# communication.net
KiCad netlist of a schematic drawn in EAGLE
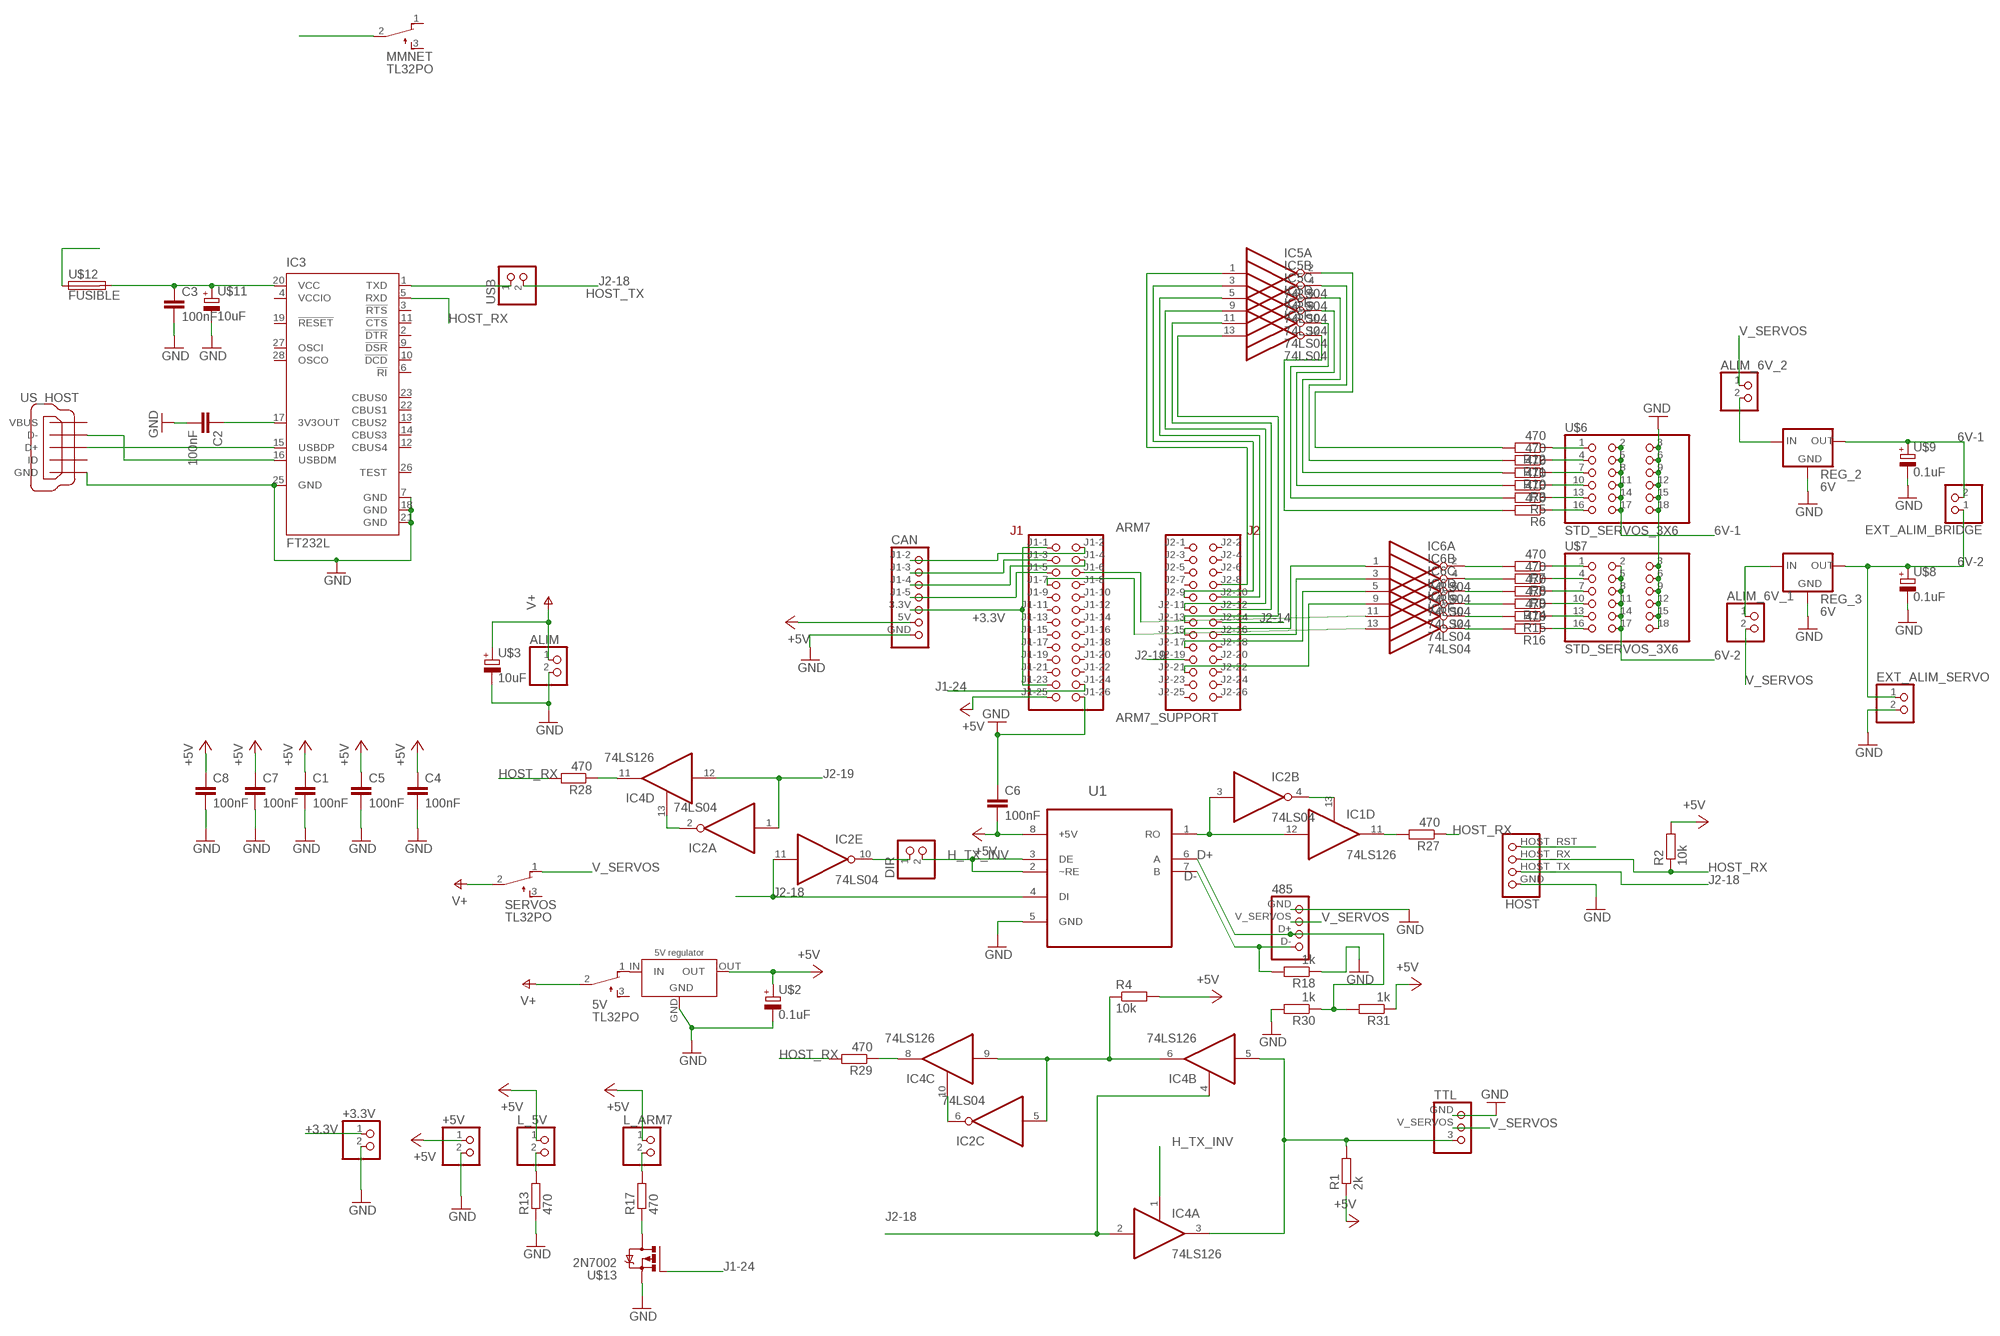
[diagram p0: schematic, sheet 1]

(export (version "E")
  (design (tool "Eeschema 10.0.6"))
  (components
    (comp (ref "+3.3V")
      (value "CONNEC_1X02")
      (footprint "eagle-import:CONNEC_1X02")
      (libsource (lib "eagle-import") (part "CONNEC_1X02"))
    )
    (comp (ref "+5V")
      (value "CONNEC_1X02")
      (footprint "eagle-import:CONNEC_1X02")
      (libsource (lib "eagle-import") (part "CONNEC_1X02"))
    )
    (comp (ref "5V")
      (value "TL32PO")
      (footprint "eagle-import:TL3XPO")
      (libsource (lib "eagle-import") (part "TL32PO"))
    )
    (comp (ref "485")
      (value "CONNECTEUR_485")
      (footprint "eagle-import:CONNECTEUR_485")
      (libsource (lib "eagle-import") (part "CONNECTEUR_485"))
    )
    (comp (ref "ALIM")
      (value "CONNEC_1X02CONNEC_1X02_LARGE")
      (footprint "eagle-import:CONNEC_ALIM")
      (libsource (lib "eagle-import") (part "CONNEC_1X02CONNEC_1X02_LARGE"))
    )
    (comp (ref "ALIM_6V_1")
      (value "CONNEC_1X02")
      (footprint "eagle-import:CONNEC_1X02")
      (libsource (lib "eagle-import") (part "CONNEC_1X02"))
    )
    (comp (ref "ALIM_6V_2")
      (value "CONNEC_1X02")
      (footprint "eagle-import:CONNEC_1X02")
      (libsource (lib "eagle-import") (part "CONNEC_1X02"))
    )
    (comp (ref "ARM7")
      (value "ARM7_SUPPORT")
      (footprint "eagle-import:ARM7_SUPPORT")
      (libsource (lib "eagle-import") (part "ARM7_SUPPORT"))
    )
    (comp (ref "C1")
      (value "100nF")
      (footprint "eagle-import:R0805")
      (libsource (lib "eagle-import") (part "C_EU_0805"))
    )
    (comp (ref "C2")
      (value "100nF")
      (footprint "eagle-import:R0805")
      (libsource (lib "eagle-import") (part "C_EU_0805"))
    )
    (comp (ref "C3")
      (value "100nF")
      (footprint "eagle-import:R0805")
      (libsource (lib "eagle-import") (part "C_EU_0805"))
    )
    (comp (ref "C4")
      (value "100nF")
      (footprint "eagle-import:R0805")
      (libsource (lib "eagle-import") (part "C_EU_0805"))
    )
    (comp (ref "C5")
      (value "100nF")
      (footprint "eagle-import:R0805")
      (libsource (lib "eagle-import") (part "C_EU_0805"))
    )
    (comp (ref "C6")
      (value "100nF")
      (footprint "eagle-import:R0805")
      (libsource (lib "eagle-import") (part "C_EU_0805"))
    )
    (comp (ref "C7")
      (value "100nF")
      (footprint "eagle-import:R0805")
      (libsource (lib "eagle-import") (part "C_EU_0805"))
    )
    (comp (ref "C8")
      (value "100nF")
      (footprint "eagle-import:R0805")
      (libsource (lib "eagle-import") (part "C_EU_0805"))
    )
    (comp (ref "CAN")
      (value "CONNECTEUR_CAN")
      (footprint "eagle-import:CONNECTEUR_CAN")
      (libsource (lib "eagle-import") (part "CONNECTEUR_CAN"))
    )
    (comp (ref "DIR")
      (value "CONNEC_1X02")
      (footprint "eagle-import:CONNEC_1X02")
      (libsource (lib "eagle-import") (part "CONNEC_1X02"))
    )
    (comp (ref "EXT_ALIM_BRIDGE")
      (value "CONNEC_1X02")
      (footprint "eagle-import:CONNEC_1X02")
      (libsource (lib "eagle-import") (part "CONNEC_1X02"))
    )
    (comp (ref "EXT_ALIM_SERVO")
      (value "CONNEC_1X02CONNEC_1X02_LARGE")
      (footprint "eagle-import:CONNEC_ALIM")
      (libsource (lib "eagle-import") (part "CONNEC_1X02CONNEC_1X02_LARGE"))
    )
    (comp (ref "HOST")
      (value "CONNECTOR_HOST")
      (footprint "eagle-import:CONNECTOR_HOST")
      (libsource (lib "eagle-import") (part "CONNECTOR_HOST"))
    )
    (comp (ref "IC1")
      (value "74LS126")
      (footprint "eagle-import:SO14")
      (libsource (lib "eagle-import") (part "74126DLS"))
    )
    (comp (ref "IC2")
      (value "74LS04")
      (footprint "eagle-import:SO14")
      (libsource (lib "eagle-import") (part "7404DLS"))
    )
    (comp (ref "IC3")
      (value "FT232L")
      (footprint "eagle-import:SSOP28")
      (fields (field (name "MPN") "FT232RL"))
      (libsource (lib "eagle-import") (part "FT232L"))
    )
    (comp (ref "IC4")
      (value "74LS126")
      (footprint "eagle-import:SO14")
      (libsource (lib "eagle-import") (part "74126DLS"))
    )
    (comp (ref "IC5")
      (value "74LS04")
      (footprint "eagle-import:SO14")
      (libsource (lib "eagle-import") (part "7404DLS"))
    )
    (comp (ref "IC6")
      (value "74LS04")
      (footprint "eagle-import:SO14")
      (libsource (lib "eagle-import") (part "7404DLS"))
    )
    (comp (ref "L_5V")
      (value "CONNEC_1X02")
      (footprint "eagle-import:CONNEC_1X02")
      (libsource (lib "eagle-import") (part "CONNEC_1X02"))
    )
    (comp (ref "L_ARM7")
      (value "CONNEC_1X02")
      (footprint "eagle-import:CONNEC_1X02")
      (libsource (lib "eagle-import") (part "CONNEC_1X02"))
    )
    (comp (ref "MMNET")
      (value "TL32PO")
      (footprint "eagle-import:TL3XPO")
      (libsource (lib "eagle-import") (part "TL32PO"))
    )
    (comp (ref "R1")
      (value "2k")
      (footprint "eagle-import:R0805@1")
      (libsource (lib "eagle-import") (part "R-EU_R0805"))
    )
    (comp (ref "R2")
      (value "10k")
      (footprint "eagle-import:R0805@1")
      (libsource (lib "eagle-import") (part "R-EU_R0805"))
    )
    (comp (ref "R3")
      (value "470")
      (footprint "eagle-import:R0805@1")
      (libsource (lib "eagle-import") (part "R-EU_R0805"))
    )
    (comp (ref "R4")
      (value "10k")
      (footprint "eagle-import:R0805@1")
      (libsource (lib "eagle-import") (part "R-EU_R0805"))
    )
    (comp (ref "R5")
      (value "470")
      (footprint "eagle-import:R0805@1")
      (libsource (lib "eagle-import") (part "R-EU_R0805"))
    )
    (comp (ref "R6")
      (value "470")
      (footprint "eagle-import:R0805@1")
      (libsource (lib "eagle-import") (part "R-EU_R0805"))
    )
    (comp (ref "R7")
      (value "470")
      (footprint "eagle-import:R0805@1")
      (libsource (lib "eagle-import") (part "R-EU_R0805"))
    )
    (comp (ref "R8")
      (value "470")
      (footprint "eagle-import:R0805@1")
      (libsource (lib "eagle-import") (part "R-EU_R0805"))
    )
    (comp (ref "R9")
      (value "470")
      (footprint "eagle-import:R0805@1")
      (libsource (lib "eagle-import") (part "R-EU_R0805"))
    )
    (comp (ref "R10")
      (value "470")
      (footprint "eagle-import:R0805@1")
      (libsource (lib "eagle-import") (part "R-EU_R0805"))
    )
    (comp (ref "R11")
      (value "470")
      (footprint "eagle-import:R0805@1")
      (libsource (lib "eagle-import") (part "R-EU_R0805"))
    )
    (comp (ref "R12")
      (value "470")
      (footprint "eagle-import:R0805@1")
      (libsource (lib "eagle-import") (part "R-EU_R0805"))
    )
    (comp (ref "R13")
      (value "470")
      (footprint "eagle-import:R0805@1")
      (libsource (lib "eagle-import") (part "R-EU_R0805"))
    )
    (comp (ref "R14")
      (value "470")
      (footprint "eagle-import:R0805@1")
      (libsource (lib "eagle-import") (part "R-EU_R0805"))
    )
    (comp (ref "R15")
      (value "470")
      (footprint "eagle-import:R0805@1")
      (libsource (lib "eagle-import") (part "R-EU_R0805"))
    )
    (comp (ref "R16")
      (value "470")
      (footprint "eagle-import:R0805@1")
      (libsource (lib "eagle-import") (part "R-EU_R0805"))
    )
    (comp (ref "R17")
      (value "470")
      (footprint "eagle-import:R0805@1")
      (libsource (lib "eagle-import") (part "R-EU_R0805"))
    )
    (comp (ref "R18")
      (value "1k")
      (footprint "eagle-import:R0805@1")
      (libsource (lib "eagle-import") (part "R-EU_R0805"))
    )
    (comp (ref "R27")
      (value "470")
      (footprint "eagle-import:R0805@1")
      (libsource (lib "eagle-import") (part "R-EU_R0805"))
    )
    (comp (ref "R28")
      (value "470")
      (footprint "eagle-import:R0805@1")
      (libsource (lib "eagle-import") (part "R-EU_R0805"))
    )
    (comp (ref "R29")
      (value "470")
      (footprint "eagle-import:R0805@1")
      (libsource (lib "eagle-import") (part "R-EU_R0805"))
    )
    (comp (ref "R30")
      (value "1k")
      (footprint "eagle-import:R0805@1")
      (libsource (lib "eagle-import") (part "R-EU_R0805"))
    )
    (comp (ref "R31")
      (value "1k")
      (footprint "eagle-import:R0805@1")
      (libsource (lib "eagle-import") (part "R-EU_R0805"))
    )
    (comp (ref "REG_2")
      (value "6V")
      (footprint "eagle-import:78XXL")
      (libsource (lib "eagle-import") (part "78XXL"))
    )
    (comp (ref "REG_3")
      (value "6V")
      (footprint "eagle-import:78XXL")
      (libsource (lib "eagle-import") (part "78XXL"))
    )
    (comp (ref "SERVOS")
      (value "TL32PO")
      (footprint "eagle-import:TL3XPO")
      (libsource (lib "eagle-import") (part "TL32PO"))
    )
    (comp (ref "TTL")
      (value "CONNECTEUR_TTL")
      (footprint "eagle-import:CONNECTEUR_TTL")
      (libsource (lib "eagle-import") (part "CONNECTEUR_TTL"))
    )
    (comp (ref "U$2")
      (value "0.1uF")
      (footprint "eagle-import:E2,5-6")
      (libsource (lib "eagle-import") (part "CPOL_EUCPOL_EU_2.54-6"))
    )
    (comp (ref "U$3")
      (value "10uF")
      (footprint "eagle-import:E5-10,5")
      (libsource (lib "eagle-import") (part "CPOL_EUCPOL_EU_5-10,5"))
    )
    (comp (ref "U$6")
      (value "STD_SERVOS_3X6")
      (footprint "eagle-import:STD_SERVOS_3X6")
      (libsource (lib "eagle-import") (part "STD_SERVOS_3X6"))
    )
    (comp (ref "U$7")
      (value "STD_SERVOS_3X6")
      (footprint "eagle-import:STD_SERVOS_3X6")
      (libsource (lib "eagle-import") (part "STD_SERVOS_3X6"))
    )
    (comp (ref "U$8")
      (value "0.1uF")
      (footprint "eagle-import:E2,5-6")
      (libsource (lib "eagle-import") (part "CPOL_EUCPOL_EU_2.54-6"))
    )
    (comp (ref "U$9")
      (value "0.1uF")
      (footprint "eagle-import:E2,5-6")
      (libsource (lib "eagle-import") (part "CPOL_EUCPOL_EU_2.54-6"))
    )
    (comp (ref "U$11")
      (value "10uF")
      (footprint "eagle-import:E5-10,5")
      (libsource (lib "eagle-import") (part "CPOL_EUCPOL_EU_5-10,5"))
    )
    (comp (ref "U$12")
      (value "FUSIBLE")
      (footprint "eagle-import:FUSIBLE")
      (libsource (lib "eagle-import") (part "FUSIBLE"))
    )
    (comp (ref "U$13")
      (value "2N7002")
      (footprint "eagle-import:SOT-23")
      (libsource (lib "eagle-import") (part "2N7002"))
    )
    (comp (ref "U$14")
      (value "5V regulator")
      (footprint "eagle-import:REGULATEUR_CMS")
      (libsource (lib "eagle-import") (part "REGULATEUR_CMS"))
    )
    (comp (ref "U1")
      (value "MAX485EESA+")
      (footprint "eagle-import:SOIC127P600X175-8N")
      (libsource (lib "eagle-import") (part "MAX485EESA+"))
    )
    (comp (ref "USB")
      (value "CONNEC_1X02")
      (footprint "eagle-import:CONNEC_1X02")
      (libsource (lib "eagle-import") (part "CONNEC_1X02"))
    )
    (comp (ref "US_HOST")
      (value "MINIUSB")
      (footprint "eagle-import:MINI_USB")
      (libsource (lib "eagle-import") (part "MINIUSB"))
    )
  )
  (nets
    (net (code "1") (name "+5V") (class "Default")
      (node (ref "+5V") (pin "1") (pinfunction "1_1") (pintype "passive"))
      (node (ref "ARM7") (pin "J1-25") (pinfunction "25_J1-25") (pintype "passive"))
      (node (ref "C1") (pin "1") (pinfunction "1_1") (pintype "passive"))
      (node (ref "C3") (pin "1") (pinfunction "1_1") (pintype "passive"))
      (node (ref "C4") (pin "1") (pinfunction "1_1") (pintype "passive"))
      (node (ref "C5") (pin "1") (pinfunction "1_1") (pintype "passive"))
      (node (ref "C6") (pin "2") (pinfunction "2_2") (pintype "passive"))
      (node (ref "C7") (pin "1") (pinfunction "1_1") (pintype "passive"))
      (node (ref "C8") (pin "1") (pinfunction "1_1") (pintype "passive"))
      (node (ref "CAN") (pin "5V") (pinfunction "5V_5V") (pintype "passive"))
      (node (ref "IC3") (pin "20") (pinfunction "VCC_20") (pintype "power_in"))
      (node (ref "L_5V") (pin "1") (pinfunction "1_1") (pintype "passive"))
      (node (ref "L_ARM7") (pin "1") (pinfunction "1_1") (pintype "passive"))
      (node (ref "R1") (pin "1") (pinfunction "1_1") (pintype "passive"))
      (node (ref "R2") (pin "2") (pinfunction "2_2") (pintype "passive"))
      (node (ref "R31") (pin "1") (pinfunction "1_1") (pintype "passive"))
      (node (ref "R4") (pin "2") (pinfunction "2_2") (pintype "passive"))
      (node (ref "U$11") (pin "+") (pinfunction "+_+") (pintype "passive"))
      (node (ref "U$12") (pin "P$1") (pinfunction "1_P$1") (pintype "passive"))
      (node (ref "U$12") (pin "P$2") (pinfunction "2_P$2") (pintype "passive"))
      (node (ref "U$14") (pin "OUT") (pinfunction "OUT_OUT") (pintype "output"))
      (node (ref "U$2") (pin "+") (pinfunction "+_+") (pintype "passive"))
      (node (ref "U1") (pin "8") (pinfunction "+5V_8") (pintype "power_in"))
    )
    (net (code "2") (name "/+3.3V") (class "Default")
      (node (ref "+3.3V") (pin "1") (pinfunction "1_1") (pintype "passive"))
      (node (ref "ARM7") (pin "J1-1") (pinfunction "1_J1-1") (pintype "passive"))
      (node (ref "ARM7") (pin "J1-23") (pinfunction "23_J1-23") (pintype "passive"))
      (node (ref "CAN") (pin "3.3V") (pinfunction "3.3V_3.3V") (pintype "passive"))
    )
    (net (code "3") (name "/6V-1") (class "Default")
      (node (ref "EXT_ALIM_BRIDGE") (pin "2") (pinfunction "2_2") (pintype "passive"))
      (node (ref "REG_2") (pin "OUT") (pinfunction "OUT_OUT") (pintype "passive"))
      (node (ref "U$6") (pin "11") (pinfunction "11_11") (pintype "passive"))
      (node (ref "U$6") (pin "14") (pinfunction "14_14") (pintype "passive"))
      (node (ref "U$6") (pin "17") (pinfunction "17_17") (pintype "passive"))
      (node (ref "U$6") (pin "2") (pinfunction "2_2") (pintype "passive"))
      (node (ref "U$6") (pin "5") (pinfunction "5_5") (pintype "passive"))
      (node (ref "U$6") (pin "8") (pinfunction "8_8") (pintype "passive"))
      (node (ref "U$9") (pin "+") (pinfunction "+_+") (pintype "passive"))
    )
    (net (code "4") (name "/6V-2") (class "Default")
      (node (ref "EXT_ALIM_BRIDGE") (pin "1") (pinfunction "1_1") (pintype "passive"))
      (node (ref "EXT_ALIM_SERVO") (pin "1") (pinfunction "1_1") (pintype "passive"))
      (node (ref "REG_3") (pin "OUT") (pinfunction "OUT_OUT") (pintype "passive"))
      (node (ref "U$7") (pin "11") (pinfunction "11_11") (pintype "passive"))
      (node (ref "U$7") (pin "14") (pinfunction "14_14") (pintype "passive"))
      (node (ref "U$7") (pin "17") (pinfunction "17_17") (pintype "passive"))
      (node (ref "U$7") (pin "2") (pinfunction "2_2") (pintype "passive"))
      (node (ref "U$7") (pin "5") (pinfunction "5_5") (pintype "passive"))
      (node (ref "U$7") (pin "8") (pinfunction "8_8") (pintype "passive"))
      (node (ref "U$8") (pin "+") (pinfunction "+_+") (pintype "passive"))
    )
    (net (code "5") (name "/D+") (class "Default")
      (node (ref "485") (pin "D+") (pinfunction "D+_D+") (pintype "passive"))
      (node (ref "R30") (pin "1") (pinfunction "1_1") (pintype "passive"))
      (node (ref "R31") (pin "2") (pinfunction "2_2") (pintype "passive"))
      (node (ref "U1") (pin "6") (pinfunction "A_6") (pintype "bidirectional"))
    )
    (net (code "6") (name "/D-") (class "Default")
      (node (ref "485") (pin "D-") (pinfunction "D-_D-") (pintype "passive"))
      (node (ref "R18") (pin "2") (pinfunction "2_2") (pintype "passive"))
      (node (ref "U1") (pin "7") (pinfunction "B_7") (pintype "bidirectional"))
    )
    (net (code "7") (name "/HOST_RX") (class "Default")
      (node (ref "HOST") (pin "HOST_RX") (pinfunction "HOST_RX_HOST_RX") (pintype "passive"))
      (node (ref "IC3") (pin "5") (pinfunction "RXD_5") (pintype "input"))
      (node (ref "R2") (pin "1") (pinfunction "1_1") (pintype "passive"))
      (node (ref "R27") (pin "1") (pinfunction "1_1") (pintype "passive"))
      (node (ref "R28") (pin "2") (pinfunction "2_2") (pintype "passive"))
      (node (ref "R29") (pin "2") (pinfunction "2_2") (pintype "passive"))
    )
    (net (code "8") (name "/H_TX_INV") (class "Default")
      (node (ref "DIR") (pin "2") (pinfunction "2_2") (pintype "passive"))
      (node (ref "HOST") (pin "HOST_RST") (pinfunction "HOST_RST_HOST_RST") (pintype "passive"))
      (node (ref "IC4") (pin "1") (pinfunction "OE_1") (pintype "input"))
      (node (ref "U1") (pin "2") (pinfunction "~{RE}_2") (pintype "input"))
      (node (ref "U1") (pin "3") (pinfunction "DE_3") (pintype "input"))
    )
    (net (code "9") (name "/J1-24") (class "Default")
      (node (ref "ARM7") (pin "J1-24") (pinfunction "24_J1-24") (pintype "passive"))
      (node (ref "U$13") (pin "1") (pinfunction "G_1") (pintype "passive"))
    )
    (net (code "10") (name "/J2-14") (class "Default")
      (node (ref "ARM7") (pin "J2-14") (pinfunction "40_J2-14") (pintype "passive"))
    )
    (net (code "11") (name "/J2-18") (class "Default")
      (node (ref "HOST") (pin "HOST_TX") (pinfunction "HOST_TX_HOST_TX") (pintype "passive"))
      (node (ref "IC2") (pin "11") (pinfunction "I_11") (pintype "input"))
      (node (ref "IC4") (pin "2") (pinfunction "I_2") (pintype "input"))
      (node (ref "IC4") (pin "4") (pinfunction "OE_4") (pintype "input"))
      (node (ref "U1") (pin "4") (pinfunction "DI_4") (pintype "input"))
      (node (ref "USB") (pin "2") (pinfunction "2_2") (pintype "passive"))
    )
    (net (code "12") (name "/J2-19") (class "Default")
      (node (ref "ARM7") (pin "J2-19") (pinfunction "45_J2-19") (pintype "passive"))
      (node (ref "IC2") (pin "1") (pinfunction "I_1") (pintype "input"))
      (node (ref "IC4") (pin "12") (pinfunction "I_12") (pintype "input"))
    )
    (net (code "13") (name "/VCCIO") (class "Default")
      (node (ref "IC3") (pin "4") (pinfunction "VCCIO_4") (pintype "power_in"))
    )
    (net (code "14") (name "/V_SERVOS") (class "Default")
      (node (ref "485") (pin "V_SERVOS") (pinfunction "V_SERVOS_V_SERVOS") (pintype "passive"))
      (node (ref "ALIM_6V_1") (pin "2") (pinfunction "2_2") (pintype "passive"))
      (node (ref "ALIM_6V_2") (pin "1") (pinfunction "1_1") (pintype "passive"))
      (node (ref "SERVOS") (pin "1") (pinfunction "O_1") (pintype "passive"))
      (node (ref "TTL") (pin "V_SERVOS") (pinfunction "V_SERVOS_V_SERVOS") (pintype "passive"))
    )
    (net (code "15") (name "GND") (class "Default")
      (node (ref "+3.3V") (pin "2") (pinfunction "2_2") (pintype "passive"))
      (node (ref "+5V") (pin "2") (pinfunction "2_2") (pintype "passive"))
      (node (ref "485") (pin "GND") (pinfunction "GND_GND") (pintype "passive"))
      (node (ref "ALIM") (pin "2") (pinfunction "2_2") (pintype "passive"))
      (node (ref "ARM7") (pin "J1-26") (pinfunction "26_J1-26") (pintype "passive"))
      (node (ref "C1") (pin "2") (pinfunction "2_2") (pintype "passive"))
      (node (ref "C2") (pin "2") (pinfunction "2_2") (pintype "passive"))
      (node (ref "C3") (pin "2") (pinfunction "2_2") (pintype "passive"))
      (node (ref "C4") (pin "2") (pinfunction "2_2") (pintype "passive"))
      (node (ref "C5") (pin "2") (pinfunction "2_2") (pintype "passive"))
      (node (ref "C6") (pin "1") (pinfunction "1_1") (pintype "passive"))
      (node (ref "C7") (pin "2") (pinfunction "2_2") (pintype "passive"))
      (node (ref "C8") (pin "2") (pinfunction "2_2") (pintype "passive"))
      (node (ref "CAN") (pin "GND") (pinfunction "GND_GND") (pintype "passive"))
      (node (ref "EXT_ALIM_SERVO") (pin "2") (pinfunction "2_2") (pintype "passive"))
      (node (ref "HOST") (pin "GND") (pinfunction "GND_GND") (pintype "passive"))
      (node (ref "IC3") (pin "18") (pinfunction "GND_18") (pintype "power_in"))
      (node (ref "IC3") (pin "21") (pinfunction "GND_21") (pintype "power_in"))
      (node (ref "IC3") (pin "25") (pinfunction "GND_25") (pintype "power_in"))
      (node (ref "IC3") (pin "7") (pinfunction "GND_7") (pintype "power_in"))
      (node (ref "R13") (pin "1") (pinfunction "1_1") (pintype "passive"))
      (node (ref "R18") (pin "1") (pinfunction "1_1") (pintype "passive"))
      (node (ref "R30") (pin "2") (pinfunction "2_2") (pintype "passive"))
      (node (ref "REG_2") (pin "GND") (pinfunction "GND_GND") (pintype "input"))
      (node (ref "REG_3") (pin "GND") (pinfunction "GND_GND") (pintype "input"))
      (node (ref "TTL") (pin "GND") (pinfunction "GND_GND") (pintype "passive"))
      (node (ref "U$11") (pin "-") (pinfunction "-_-") (pintype "passive"))
      (node (ref "U$13") (pin "2") (pinfunction "S_2") (pintype "passive"))
      (node (ref "U$14") (pin "GND") (pinfunction "GND_GND") (pintype "power_in"))
      (node (ref "U$2") (pin "-") (pinfunction "-_-") (pintype "passive"))
      (node (ref "U$3") (pin "-") (pinfunction "-_-") (pintype "passive"))
      (node (ref "U$6") (pin "12") (pinfunction "12_12") (pintype "passive"))
      (node (ref "U$6") (pin "15") (pinfunction "15_15") (pintype "passive"))
      (node (ref "U$6") (pin "18") (pinfunction "18_18") (pintype "passive"))
      (node (ref "U$6") (pin "3") (pinfunction "3_3") (pintype "passive"))
      (node (ref "U$6") (pin "6") (pinfunction "6_6") (pintype "passive"))
      (node (ref "U$6") (pin "9") (pinfunction "9_9") (pintype "passive"))
      (node (ref "U$7") (pin "12") (pinfunction "12_12") (pintype "passive"))
      (node (ref "U$7") (pin "15") (pinfunction "15_15") (pintype "passive"))
      (node (ref "U$7") (pin "18") (pinfunction "18_18") (pintype "passive"))
      (node (ref "U$7") (pin "3") (pinfunction "3_3") (pintype "passive"))
      (node (ref "U$7") (pin "6") (pinfunction "6_6") (pintype "passive"))
      (node (ref "U$7") (pin "9") (pinfunction "9_9") (pintype "passive"))
      (node (ref "U$8") (pin "-") (pinfunction "-_-") (pintype "passive"))
      (node (ref "U$9") (pin "-") (pinfunction "-_-") (pintype "passive"))
      (node (ref "U1") (pin "5") (pinfunction "GND_5") (pintype "passive"))
      (node (ref "US_HOST") (pin "GND") (pinfunction "GND_GND") (pintype "passive"))
    )
    (net (code "16") (name "Net-(5V-O)") (class "Default")
      (node (ref "5V") (pin "1") (pinfunction "O_1") (pintype "passive"))
      (node (ref "U$14") (pin "IN") (pinfunction "IN_IN") (pintype "input"))
    )
    (net (code "17") (name "Net-(ALIM_6V_1-Pad1)") (class "Default")
      (node (ref "ALIM_6V_1") (pin "1") (pinfunction "1_1") (pintype "passive"))
      (node (ref "REG_3") (pin "IN") (pinfunction "IN_IN") (pintype "input"))
    )
    (net (code "18") (name "Net-(ALIM_6V_2-Pad2)") (class "Default")
      (node (ref "ALIM_6V_2") (pin "2") (pinfunction "2_2") (pintype "passive"))
      (node (ref "REG_2") (pin "IN") (pinfunction "IN_IN") (pintype "input"))
    )
    (net (code "19") (name "Net-(ARM7-2)") (class "Default")
      (node (ref "ARM7") (pin "J1-2") (pinfunction "2_J1-2") (pintype "passive"))
      (node (ref "CAN") (pin "J1-2") (pinfunction "J1-2_J1-2") (pintype "passive"))
    )
    (net (code "20") (name "Net-(ARM7-3)") (class "Default")
      (node (ref "ARM7") (pin "J1-3") (pinfunction "3_J1-3") (pintype "passive"))
      (node (ref "CAN") (pin "J1-3") (pinfunction "J1-3_J1-3") (pintype "passive"))
    )
    (net (code "21") (name "Net-(ARM7-4)") (class "Default")
      (node (ref "ARM7") (pin "J1-4") (pinfunction "4_J1-4") (pintype "passive"))
      (node (ref "CAN") (pin "J1-4") (pinfunction "J1-4_J1-4") (pintype "passive"))
    )
    (net (code "22") (name "Net-(ARM7-5)") (class "Default")
      (node (ref "ARM7") (pin "J1-5") (pinfunction "5_J1-5") (pintype "passive"))
      (node (ref "CAN") (pin "J1-5") (pinfunction "J1-5_J1-5") (pintype "passive"))
    )
    (net (code "23") (name "Net-(ARM7-6)") (class "Default")
      (node (ref "ARM7") (pin "J1-6") (pinfunction "6_J1-6") (pintype "passive"))
      (node (ref "IC6") (pin "11") (pinfunction "I_11") (pintype "input"))
    )
    (net (code "24") (name "Net-(ARM7-7)") (class "Default")
      (node (ref "ARM7") (pin "J1-7") (pinfunction "7_J1-7") (pintype "passive"))
      (node (ref "IC6") (pin "13") (pinfunction "I_13") (pintype "input"))
    )
    (net (code "25") (name "Net-(ARM7-34)") (class "Default")
      (node (ref "ARM7") (pin "J2-8") (pinfunction "34_J2-8") (pintype "passive"))
      (node (ref "IC5") (pin "1") (pinfunction "I_1") (pintype "input"))
    )
    (net (code "26") (name "Net-(ARM7-35)") (class "Default")
      (node (ref "ARM7") (pin "J2-9") (pinfunction "35_J2-9") (pintype "passive"))
      (node (ref "IC5") (pin "3") (pinfunction "I_3") (pintype "input"))
    )
    (net (code "27") (name "Net-(ARM7-36)") (class "Default")
      (node (ref "ARM7") (pin "J2-10") (pinfunction "36_J2-10") (pintype "passive"))
      (node (ref "IC5") (pin "5") (pinfunction "I_5") (pintype "input"))
    )
    (net (code "28") (name "Net-(ARM7-37)") (class "Default")
      (node (ref "ARM7") (pin "J2-11") (pinfunction "37_J2-11") (pintype "passive"))
      (node (ref "IC5") (pin "9") (pinfunction "I_9") (pintype "input"))
    )
    (net (code "29") (name "Net-(ARM7-38)") (class "Default")
      (node (ref "ARM7") (pin "J2-12") (pinfunction "38_J2-12") (pintype "passive"))
      (node (ref "IC5") (pin "11") (pinfunction "I_11") (pintype "input"))
    )
    (net (code "30") (name "Net-(ARM7-39)") (class "Default")
      (node (ref "ARM7") (pin "J2-13") (pinfunction "39_J2-13") (pintype "passive"))
      (node (ref "IC5") (pin "13") (pinfunction "I_13") (pintype "input"))
    )
    (net (code "31") (name "Net-(ARM7-41)") (class "Default")
      (node (ref "ARM7") (pin "J2-15") (pinfunction "41_J2-15") (pintype "passive"))
      (node (ref "IC6") (pin "1") (pinfunction "I_1") (pintype "input"))
    )
    (net (code "32") (name "Net-(ARM7-42)") (class "Default")
      (node (ref "ARM7") (pin "J2-16") (pinfunction "42_J2-16") (pintype "passive"))
      (node (ref "IC6") (pin "3") (pinfunction "I_3") (pintype "input"))
    )
    (net (code "33") (name "Net-(ARM7-43)") (class "Default")
      (node (ref "ARM7") (pin "J2-17") (pinfunction "43_J2-17") (pintype "passive"))
      (node (ref "IC6") (pin "5") (pinfunction "I_5") (pintype "input"))
    )
    (net (code "34") (name "Net-(ARM7-47)") (class "Default")
      (node (ref "ARM7") (pin "J2-21") (pinfunction "47_J2-21") (pintype "passive"))
      (node (ref "IC6") (pin "9") (pinfunction "I_9") (pintype "input"))
    )
    (net (code "35") (name "Net-(IC1D-I)") (class "Default")
      (node (ref "IC1") (pin "12") (pinfunction "I_12") (pintype "input"))
      (node (ref "IC2") (pin "3") (pinfunction "I_3") (pintype "input"))
      (node (ref "U1") (pin "1") (pinfunction "RO_1") (pintype "output"))
    )
    (net (code "36") (name "Net-(IC1D-O)") (class "Default")
      (node (ref "IC1") (pin "11") (pinfunction "O_11") (pintype "output"))
      (node (ref "R27") (pin "2") (pinfunction "2_2") (pintype "passive"))
    )
    (net (code "37") (name "Net-(IC1D-OE)") (class "Default")
      (node (ref "IC1") (pin "13") (pinfunction "OE_13") (pintype "input"))
      (node (ref "IC2") (pin "4") (pinfunction "O_4") (pintype "output"))
    )
    (net (code "38") (name "Net-(IC2A-O)") (class "Default")
      (node (ref "IC2") (pin "2") (pinfunction "O_2") (pintype "output"))
      (node (ref "IC4") (pin "13") (pinfunction "OE_13") (pintype "input"))
    )
    (net (code "39") (name "Net-(IC2C-I)") (class "Default")
      (node (ref "IC2") (pin "5") (pinfunction "I_5") (pintype "input"))
      (node (ref "IC4") (pin "6") (pinfunction "O_6") (pintype "output"))
      (node (ref "IC4") (pin "9") (pinfunction "I_9") (pintype "input"))
      (node (ref "R4") (pin "1") (pinfunction "1_1") (pintype "passive"))
    )
    (net (code "40") (name "Net-(IC2C-O)") (class "Default")
      (node (ref "IC2") (pin "6") (pinfunction "O_6") (pintype "output"))
      (node (ref "IC4") (pin "10") (pinfunction "OE_10") (pintype "input"))
    )
    (net (code "41") (name "Net-(IC2E-O)") (class "Default")
      (node (ref "DIR") (pin "1") (pinfunction "1_1") (pintype "passive"))
      (node (ref "IC2") (pin "10") (pinfunction "O_10") (pintype "output"))
    )
    (net (code "42") (name "Net-(IC3-3V3OUT)") (class "Default")
      (node (ref "C2") (pin "1") (pinfunction "1_1") (pintype "passive"))
      (node (ref "IC3") (pin "17") (pinfunction "3V3OUT_17") (pintype "output"))
    )
    (net (code "43") (name "Net-(IC3-TXD)") (class "Default")
      (node (ref "IC3") (pin "1") (pinfunction "TXD_1") (pintype "output"))
      (node (ref "USB") (pin "1") (pinfunction "1_1") (pintype "passive"))
    )
    (net (code "44") (name "Net-(IC3-USBDM)") (class "Default")
      (node (ref "IC3") (pin "16") (pinfunction "USBDM_16") (pintype "bidirectional"))
      (node (ref "US_HOST") (pin "D-") (pinfunction "D-_D-") (pintype "passive"))
    )
    (net (code "45") (name "Net-(IC3-USBDP)") (class "Default")
      (node (ref "IC3") (pin "15") (pinfunction "USBDP_15") (pintype "bidirectional"))
      (node (ref "US_HOST") (pin "D+") (pinfunction "D+_D+") (pintype "passive"))
    )
    (net (code "46") (name "Net-(IC4A-O)") (class "Default")
      (node (ref "IC4") (pin "3") (pinfunction "O_3") (pintype "output"))
      (node (ref "IC4") (pin "5") (pinfunction "I_5") (pintype "input"))
      (node (ref "R1") (pin "2") (pinfunction "2_2") (pintype "passive"))
      (node (ref "TTL") (pin "3") (pinfunction "3_3") (pintype "passive"))
    )
    (net (code "47") (name "Net-(IC4C-O)") (class "Default")
      (node (ref "IC4") (pin "8") (pinfunction "O_8") (pintype "output"))
      (node (ref "R29") (pin "1") (pinfunction "1_1") (pintype "passive"))
    )
    (net (code "48") (name "Net-(IC4D-O)") (class "Default")
      (node (ref "IC4") (pin "11") (pinfunction "O_11") (pintype "output"))
      (node (ref "R28") (pin "1") (pinfunction "1_1") (pintype "passive"))
    )
    (net (code "49") (name "Net-(IC5A-O)") (class "Default")
      (node (ref "IC5") (pin "2") (pinfunction "O_2") (pintype "output"))
      (node (ref "R12") (pin "2") (pinfunction "2_2") (pintype "passive"))
    )
    (net (code "50") (name "Net-(IC5B-O)") (class "Default")
      (node (ref "IC5") (pin "4") (pinfunction "O_4") (pintype "output"))
      (node (ref "R11") (pin "2") (pinfunction "2_2") (pintype "passive"))
    )
    (net (code "51") (name "Net-(IC5C-O)") (class "Default")
      (node (ref "IC5") (pin "6") (pinfunction "O_6") (pintype "output"))
      (node (ref "R10") (pin "2") (pinfunction "2_2") (pintype "passive"))
    )
    (net (code "52") (name "Net-(IC5D-O)") (class "Default")
      (node (ref "IC5") (pin "8") (pinfunction "O_8") (pintype "output"))
      (node (ref "R3") (pin "2") (pinfunction "2_2") (pintype "passive"))
    )
    (net (code "53") (name "Net-(IC5E-O)") (class "Default")
      (node (ref "IC5") (pin "10") (pinfunction "O_10") (pintype "output"))
      (node (ref "R5") (pin "2") (pinfunction "2_2") (pintype "passive"))
    )
    (net (code "54") (name "Net-(IC5F-O)") (class "Default")
      (node (ref "IC5") (pin "12") (pinfunction "O_12") (pintype "output"))
      (node (ref "R6") (pin "2") (pinfunction "2_2") (pintype "passive"))
    )
    (net (code "55") (name "Net-(IC6A-O)") (class "Default")
      (node (ref "IC6") (pin "2") (pinfunction "O_2") (pintype "output"))
      (node (ref "R7") (pin "2") (pinfunction "2_2") (pintype "passive"))
    )
    (net (code "56") (name "Net-(IC6B-O)") (class "Default")
      (node (ref "IC6") (pin "4") (pinfunction "O_4") (pintype "output"))
      (node (ref "R8") (pin "2") (pinfunction "2_2") (pintype "passive"))
    )
    (net (code "57") (name "Net-(IC6C-O)") (class "Default")
      (node (ref "IC6") (pin "6") (pinfunction "O_6") (pintype "output"))
      (node (ref "R9") (pin "2") (pinfunction "2_2") (pintype "passive"))
    )
    (net (code "58") (name "Net-(IC6D-O)") (class "Default")
      (node (ref "IC6") (pin "8") (pinfunction "O_8") (pintype "output"))
      (node (ref "R14") (pin "2") (pinfunction "2_2") (pintype "passive"))
    )
    (net (code "59") (name "Net-(IC6E-O)") (class "Default")
      (node (ref "IC6") (pin "10") (pinfunction "O_10") (pintype "output"))
      (node (ref "R15") (pin "2") (pinfunction "2_2") (pintype "passive"))
    )
    (net (code "60") (name "Net-(IC6F-O)") (class "Default")
      (node (ref "IC6") (pin "12") (pinfunction "O_12") (pintype "output"))
      (node (ref "R16") (pin "2") (pinfunction "2_2") (pintype "passive"))
    )
    (net (code "61") (name "Net-(L_5V-Pad2)") (class "Default")
      (node (ref "L_5V") (pin "2") (pinfunction "2_2") (pintype "passive"))
      (node (ref "R13") (pin "2") (pinfunction "2_2") (pintype "passive"))
    )
    (net (code "62") (name "Net-(L_ARM7-Pad2)") (class "Default")
      (node (ref "L_ARM7") (pin "2") (pinfunction "2_2") (pintype "passive"))
      (node (ref "R17") (pin "2") (pinfunction "2_2") (pintype "passive"))
    )
    (net (code "63") (name "Net-(R3-Pad1)") (class "Default")
      (node (ref "R3") (pin "1") (pinfunction "1_1") (pintype "passive"))
      (node (ref "U$6") (pin "10") (pinfunction "10_10") (pintype "passive"))
    )
    (net (code "64") (name "Net-(R5-Pad1)") (class "Default")
      (node (ref "R5") (pin "1") (pinfunction "1_1") (pintype "passive"))
      (node (ref "U$6") (pin "13") (pinfunction "13_13") (pintype "passive"))
    )
    (net (code "65") (name "Net-(R6-Pad1)") (class "Default")
      (node (ref "R6") (pin "1") (pinfunction "1_1") (pintype "passive"))
      (node (ref "U$6") (pin "16") (pinfunction "16_16") (pintype "passive"))
    )
    (net (code "66") (name "Net-(R7-Pad1)") (class "Default")
      (node (ref "R7") (pin "1") (pinfunction "1_1") (pintype "passive"))
      (node (ref "U$7") (pin "1") (pinfunction "1_1") (pintype "passive"))
    )
    (net (code "67") (name "Net-(R8-Pad1)") (class "Default")
      (node (ref "R8") (pin "1") (pinfunction "1_1") (pintype "passive"))
      (node (ref "U$7") (pin "4") (pinfunction "4_4") (pintype "passive"))
    )
    (net (code "68") (name "Net-(R9-Pad1)") (class "Default")
      (node (ref "R9") (pin "1") (pinfunction "1_1") (pintype "passive"))
      (node (ref "U$7") (pin "7") (pinfunction "7_7") (pintype "passive"))
    )
    (net (code "69") (name "Net-(R10-Pad1)") (class "Default")
      (node (ref "R10") (pin "1") (pinfunction "1_1") (pintype "passive"))
      (node (ref "U$6") (pin "7") (pinfunction "7_7") (pintype "passive"))
    )
    (net (code "70") (name "Net-(R11-Pad1)") (class "Default")
      (node (ref "R11") (pin "1") (pinfunction "1_1") (pintype "passive"))
      (node (ref "U$6") (pin "4") (pinfunction "4_4") (pintype "passive"))
    )
    (net (code "71") (name "Net-(R12-Pad1)") (class "Default")
      (node (ref "R12") (pin "1") (pinfunction "1_1") (pintype "passive"))
      (node (ref "U$6") (pin "1") (pinfunction "1_1") (pintype "passive"))
    )
    (net (code "72") (name "Net-(R14-Pad1)") (class "Default")
      (node (ref "R14") (pin "1") (pinfunction "1_1") (pintype "passive"))
      (node (ref "U$7") (pin "10") (pinfunction "10_10") (pintype "passive"))
    )
    (net (code "73") (name "Net-(R15-Pad1)") (class "Default")
      (node (ref "R15") (pin "1") (pinfunction "1_1") (pintype "passive"))
      (node (ref "U$7") (pin "13") (pinfunction "13_13") (pintype "passive"))
    )
    (net (code "74") (name "Net-(R16-Pad1)") (class "Default")
      (node (ref "R16") (pin "1") (pinfunction "1_1") (pintype "passive"))
      (node (ref "U$7") (pin "16") (pinfunction "16_16") (pintype "passive"))
    )
    (net (code "75") (name "Net-(U$13-D)") (class "Default")
      (node (ref "R17") (pin "1") (pinfunction "1_1") (pintype "passive"))
      (node (ref "U$13") (pin "3") (pinfunction "D_3") (pintype "passive"))
    )
    (net (code "76") (name "V+") (class "Default")
      (node (ref "5V") (pin "2") (pinfunction "P_2") (pintype "passive"))
      (node (ref "ALIM") (pin "1") (pinfunction "1_1") (pintype "passive"))
      (node (ref "MMNET") (pin "2") (pinfunction "P_2") (pintype "passive"))
      (node (ref "SERVOS") (pin "2") (pinfunction "P_2") (pintype "passive"))
      (node (ref "U$3") (pin "+") (pinfunction "+_+") (pintype "passive"))
    )
    (net (code "77") (name "unconnected-(5V-S-Pad3)") (class "Default")
      (node (ref "5V") (pin "3") (pinfunction "S_3") (pintype "passive"))
    )
    (net (code "78") (name "unconnected-(ARM7-8-PadJ1-8)") (class "Default")
      (node (ref "ARM7") (pin "J1-8") (pinfunction "8_J1-8") (pintype "passive"))
    )
    (net (code "79") (name "unconnected-(ARM7-9-PadJ1-9)") (class "Default")
      (node (ref "ARM7") (pin "J1-9") (pinfunction "9_J1-9") (pintype "passive"))
    )
    (net (code "80") (name "unconnected-(ARM7-10-PadJ1-10)") (class "Default")
      (node (ref "ARM7") (pin "J1-10") (pinfunction "10_J1-10") (pintype "passive"))
    )
    (net (code "81") (name "unconnected-(ARM7-11-PadJ1-11)") (class "Default")
      (node (ref "ARM7") (pin "J1-11") (pinfunction "11_J1-11") (pintype "passive"))
    )
    (net (code "82") (name "unconnected-(ARM7-12-PadJ1-12)") (class "Default")
      (node (ref "ARM7") (pin "J1-12") (pinfunction "12_J1-12") (pintype "passive"))
    )
    (net (code "83") (name "unconnected-(ARM7-13-PadJ1-13)") (class "Default")
      (node (ref "ARM7") (pin "J1-13") (pinfunction "13_J1-13") (pintype "passive"))
    )
    (net (code "84") (name "unconnected-(ARM7-14-PadJ1-14)") (class "Default")
      (node (ref "ARM7") (pin "J1-14") (pinfunction "14_J1-14") (pintype "passive"))
    )
    (net (code "85") (name "unconnected-(ARM7-15-PadJ1-15)") (class "Default")
      (node (ref "ARM7") (pin "J1-15") (pinfunction "15_J1-15") (pintype "passive"))
    )
    (net (code "86") (name "unconnected-(ARM7-16-PadJ1-16)") (class "Default")
      (node (ref "ARM7") (pin "J1-16") (pinfunction "16_J1-16") (pintype "passive"))
    )
    (net (code "87") (name "unconnected-(ARM7-17-PadJ1-17)") (class "Default")
      (node (ref "ARM7") (pin "J1-17") (pinfunction "17_J1-17") (pintype "passive"))
    )
    (net (code "88") (name "unconnected-(ARM7-18-PadJ1-18)") (class "Default")
      (node (ref "ARM7") (pin "J1-18") (pinfunction "18_J1-18") (pintype "passive"))
    )
    (net (code "89") (name "unconnected-(ARM7-19-PadJ1-19)") (class "Default")
      (node (ref "ARM7") (pin "J1-19") (pinfunction "19_J1-19") (pintype "passive"))
    )
    (net (code "90") (name "unconnected-(ARM7-20-PadJ1-20)") (class "Default")
      (node (ref "ARM7") (pin "J1-20") (pinfunction "20_J1-20") (pintype "passive"))
    )
    (net (code "91") (name "unconnected-(ARM7-21-PadJ1-21)") (class "Default")
      (node (ref "ARM7") (pin "J1-21") (pinfunction "21_J1-21") (pintype "passive"))
    )
    (net (code "92") (name "unconnected-(ARM7-22-PadJ1-22)") (class "Default")
      (node (ref "ARM7") (pin "J1-22") (pinfunction "22_J1-22") (pintype "passive"))
    )
    (net (code "93") (name "unconnected-(ARM7-27-PadJ2-1)") (class "Default")
      (node (ref "ARM7") (pin "J2-1") (pinfunction "27_J2-1") (pintype "passive"))
    )
    (net (code "94") (name "unconnected-(ARM7-28-PadJ2-2)") (class "Default")
      (node (ref "ARM7") (pin "J2-2") (pinfunction "28_J2-2") (pintype "passive"))
    )
    (net (code "95") (name "unconnected-(ARM7-29-PadJ2-3)") (class "Default")
      (node (ref "ARM7") (pin "J2-3") (pinfunction "29_J2-3") (pintype "passive"))
    )
    (net (code "96") (name "unconnected-(ARM7-30-PadJ2-4)") (class "Default")
      (node (ref "ARM7") (pin "J2-4") (pinfunction "30_J2-4") (pintype "passive"))
    )
    (net (code "97") (name "unconnected-(ARM7-31-PadJ2-5)") (class "Default")
      (node (ref "ARM7") (pin "J2-5") (pinfunction "31_J2-5") (pintype "passive"))
    )
    (net (code "98") (name "unconnected-(ARM7-32-PadJ2-6)") (class "Default")
      (node (ref "ARM7") (pin "J2-6") (pinfunction "32_J2-6") (pintype "passive"))
    )
    (net (code "99") (name "unconnected-(ARM7-33-PadJ2-7)") (class "Default")
      (node (ref "ARM7") (pin "J2-7") (pinfunction "33_J2-7") (pintype "passive"))
    )
    (net (code "100") (name "unconnected-(ARM7-44-PadJ2-18)") (class "Default")
      (node (ref "ARM7") (pin "J2-18") (pinfunction "44_J2-18") (pintype "passive"))
    )
    (net (code "101") (name "unconnected-(ARM7-46-PadJ2-20)") (class "Default")
      (node (ref "ARM7") (pin "J2-20") (pinfunction "46_J2-20") (pintype "passive"))
    )
    (net (code "102") (name "unconnected-(ARM7-48-PadJ2-22)") (class "Default")
      (node (ref "ARM7") (pin "J2-22") (pinfunction "48_J2-22") (pintype "passive"))
    )
    (net (code "103") (name "unconnected-(ARM7-49-PadJ2-23)") (class "Default")
      (node (ref "ARM7") (pin "J2-23") (pinfunction "49_J2-23") (pintype "passive"))
    )
    (net (code "104") (name "unconnected-(ARM7-50-PadJ2-24)") (class "Default")
      (node (ref "ARM7") (pin "J2-24") (pinfunction "50_J2-24") (pintype "passive"))
    )
    (net (code "105") (name "unconnected-(ARM7-51-PadJ2-25)") (class "Default")
      (node (ref "ARM7") (pin "J2-25") (pinfunction "51_J2-25") (pintype "passive"))
    )
    (net (code "106") (name "unconnected-(ARM7-52-PadJ2-26)") (class "Default")
      (node (ref "ARM7") (pin "J2-26") (pinfunction "52_J2-26") (pintype "passive"))
    )
    (net (code "107") (name "unconnected-(IC3-CBUS0-Pad23)") (class "Default")
      (node (ref "IC3") (pin "23") (pinfunction "CBUS0_23") (pintype "bidirectional"))
    )
    (net (code "108") (name "unconnected-(IC3-CBUS1-Pad22)") (class "Default")
      (node (ref "IC3") (pin "22") (pinfunction "CBUS1_22") (pintype "bidirectional"))
    )
    (net (code "109") (name "unconnected-(IC3-CBUS2-Pad13)") (class "Default")
      (node (ref "IC3") (pin "13") (pinfunction "CBUS2_13") (pintype "bidirectional"))
    )
    (net (code "110") (name "unconnected-(IC3-CBUS3-Pad14)") (class "Default")
      (node (ref "IC3") (pin "14") (pinfunction "CBUS3_14") (pintype "bidirectional"))
    )
    (net (code "111") (name "unconnected-(IC3-CBUS4-Pad12)") (class "Default")
      (node (ref "IC3") (pin "12") (pinfunction "CBUS4_12") (pintype "bidirectional"))
    )
    (net (code "112") (name "unconnected-(IC3-OSCI-Pad27)") (class "Default")
      (node (ref "IC3") (pin "27") (pinfunction "OSCI_27") (pintype "input"))
    )
    (net (code "113") (name "unconnected-(IC3-OSCO-Pad28)") (class "Default")
      (node (ref "IC3") (pin "28") (pinfunction "OSCO_28") (pintype "output"))
    )
    (net (code "114") (name "unconnected-(IC3-TEST-Pad26)") (class "Default")
      (node (ref "IC3") (pin "26") (pinfunction "TEST_26") (pintype "input"))
    )
    (net (code "115") (name "unconnected-(IC3-~{CTS}-Pad11)") (class "Default")
      (node (ref "IC3") (pin "11") (pinfunction "~{CTS}_11") (pintype "input"))
    )
    (net (code "116") (name "unconnected-(IC3-~{DCD}-Pad10)") (class "Default")
      (node (ref "IC3") (pin "10") (pinfunction "~{DCD}_10") (pintype "input"))
    )
    (net (code "117") (name "unconnected-(IC3-~{DSR}-Pad9)") (class "Default")
      (node (ref "IC3") (pin "9") (pinfunction "~{DSR}_9") (pintype "input"))
    )
    (net (code "118") (name "unconnected-(IC3-~{DTR}-Pad2)") (class "Default")
      (node (ref "IC3") (pin "2") (pinfunction "~{DTR}_2") (pintype "output"))
    )
    (net (code "119") (name "unconnected-(IC3-~{RESET}-Pad19)") (class "Default")
      (node (ref "IC3") (pin "19") (pinfunction "~{RESET}_19") (pintype "input"))
    )
    (net (code "120") (name "unconnected-(IC3-~{RI}-Pad6)") (class "Default")
      (node (ref "IC3") (pin "6") (pinfunction "~{RI}_6") (pintype "input"))
    )
    (net (code "121") (name "unconnected-(IC3-~{RTS}-Pad3)") (class "Default")
      (node (ref "IC3") (pin "3") (pinfunction "~{RTS}_3") (pintype "output"))
    )
    (net (code "122") (name "unconnected-(MMNET-O-Pad1)") (class "Default")
      (node (ref "MMNET") (pin "1") (pinfunction "O_1") (pintype "passive"))
    )
    (net (code "123") (name "unconnected-(MMNET-S-Pad3)") (class "Default")
      (node (ref "MMNET") (pin "3") (pinfunction "S_3") (pintype "passive"))
    )
    (net (code "124") (name "unconnected-(SERVOS-S-Pad3)") (class "Default")
      (node (ref "SERVOS") (pin "3") (pinfunction "S_3") (pintype "passive"))
    )
    (net (code "125") (name "unconnected-(US_HOST-PadID)") (class "Default")
      (node (ref "US_HOST") (pin "ID") (pinfunction "ID_ID") (pintype "passive"))
    )
    (net (code "126") (name "unconnected-(US_HOST-PadVBUS)") (class "Default")
      (node (ref "US_HOST") (pin "VBUS") (pinfunction "VBUS_VBUS") (pintype "passive"))
    )
  )
)
